# Power.net
KiCad netlist of a schematic drawn in Altium Designer
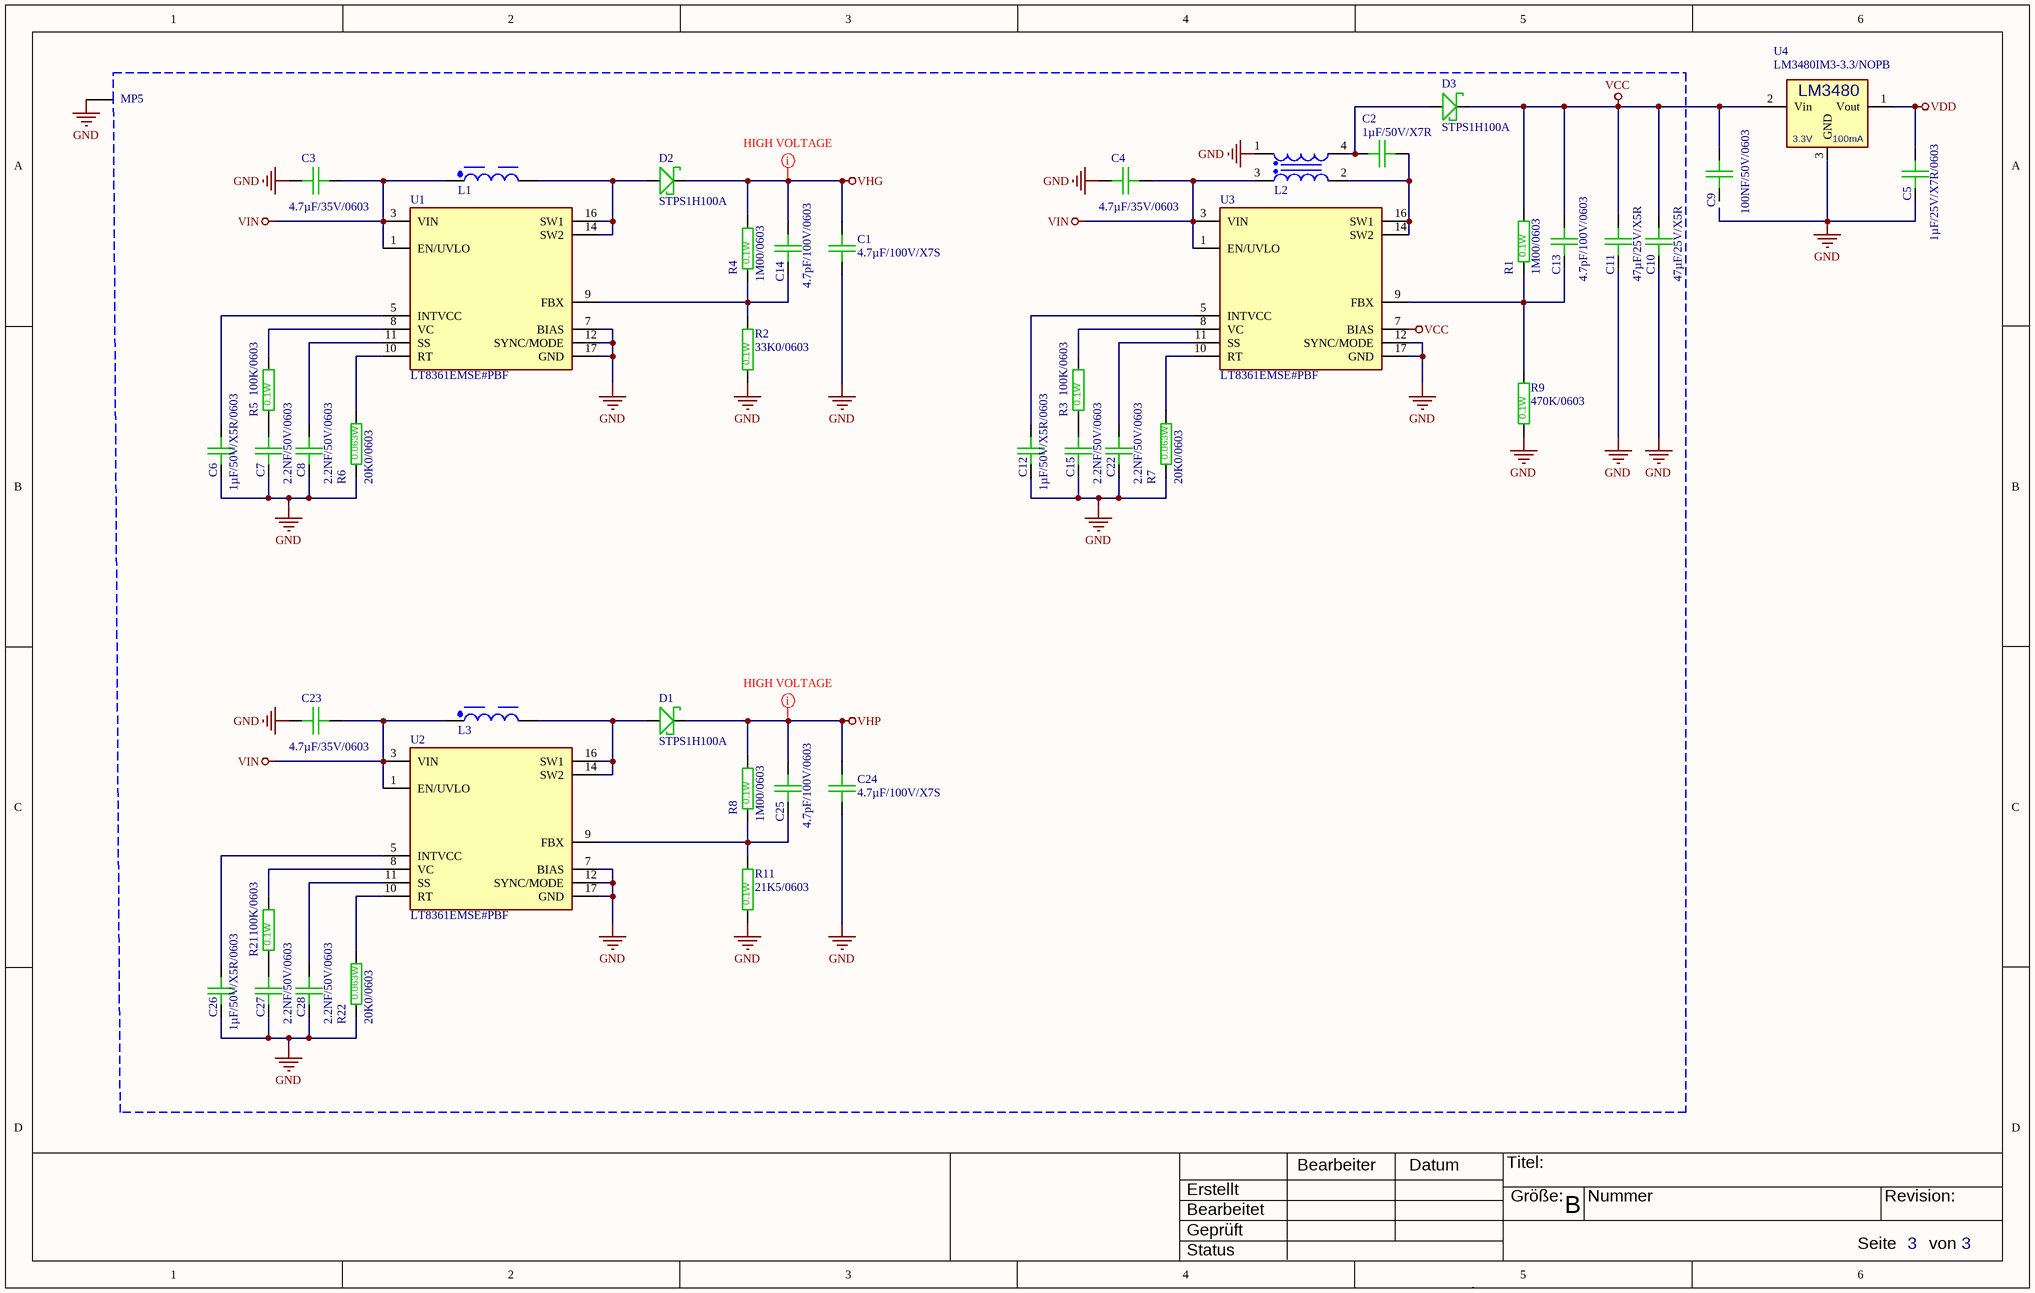
[diagram p0: Power.Schdoc]

(export (version "E")
  (design (tool "Eeschema 10.0.6"))
  (components
    (comp (ref "C1")
      (value "4.7µF/100V/X7S")
      (footprint "1206__R")
      (description "Capacitor, 4.7µF/100V, 10%, Ceramic X7S, SMD, 1206")
      (fields
        (field (name "MANUFACTURER") "Murata")
        (field (name "MANUFACTURER PART NUMBER") "GRM31CC72A475KE11L")
      )
      (libsource (lib "SCH_SMD_Passive_Capacitor_1206") (part "4.7µF/100V/X7S"))
    )
    (comp (ref "C2")
      (value "1µF/50V/X7R")
      (footprint "1206__R")
      (description "Capacitor, 1µF/50V, 10%, Ceramic X7R, SMD, 1206")
      (libsource (lib "SCH_SMD_Passive_Capacitor_1206") (part "1µF/50V"))
    )
    (comp (ref "C3")
      (value "4.7µF/35V/0603")
      (footprint "0603__R")
      (description "Capacitor, 4.7µF, 35V, 10%, Ceramic X5R, SMD, 0603, Low ESR")
      (fields
        (field (name "MANUFACTURER") "TDK")
        (field (name "MANUFACTURER PART NUMBER") "C1608X5R1V475K080AC")
      )
      (libsource (lib "SCH_SMD_Passive_Capacitor_0603") (part "4.7µF/35V/0603"))
    )
    (comp (ref "C4")
      (value "4.7µF/35V/0603")
      (footprint "0603__R")
      (description "Capacitor, 4.7µF, 35V, 10%, Ceramic X5R, SMD, 0603, Low ESR")
      (fields
        (field (name "MANUFACTURER") "TDK")
        (field (name "MANUFACTURER PART NUMBER") "C1608X5R1V475K080AC")
      )
      (libsource (lib "SCH_SMD_Passive_Capacitor_0603") (part "4.7µF/35V/0603"))
    )
    (comp (ref "C5")
      (value "1µF/25V/X7R/0603")
      (footprint "0603__R")
      (description "Capacitor, 1µF, 25V, X7R, 10%, Ceramic, SMD, 0603")
      (fields
        (field (name "MANUFACTURER") "Taiyo Yuden")
        (field (name "MANUFACTURER PART NUMBER") "TMK107B7105KA-T")
      )
      (libsource (lib "SCH_SMD_Passive_Capacitor_0603") (part "1µF/25V/X7R/0603"))
    )
    (comp (ref "C6")
      (value "1µF/50V/X5R/0603")
      (footprint "0603__R")
      (description "Capacitor, 1µF, 50V, X5R, 10%, Ceramic, SMD, 0603")
      (libsource (lib "SCH_SMD_Passive_Capacitor_0603") (part "1µF/50V/X5R/0603"))
    )
    (comp (ref "C7")
      (value "2.2NF/50V/0603")
      (footprint "0603__R")
      (description "Capacitor, 2.2nF, 50V, 10%, Ceramic, SMD, 0603")
      (fields
        (field (name "MANUFACTURER") "KEMET")
        (field (name "MANUFACTURER PART NUMBER") "C0603C222K5RAC   TU")
      )
      (libsource (lib "SCH_SMD_Passive_Capacitor_0603") (part "2.2NF/50V/0603"))
    )
    (comp (ref "C8")
      (value "2.2NF/50V/0603")
      (footprint "0603__R")
      (description "Capacitor, 2.2nF, 50V, 10%, Ceramic, SMD, 0603")
      (fields
        (field (name "MANUFACTURER") "KEMET")
        (field (name "MANUFACTURER PART NUMBER") "C0603C222K5RAC   TU")
      )
      (libsource (lib "SCH_SMD_Passive_Capacitor_0603") (part "2.2NF/50V/0603"))
    )
    (comp (ref "C9")
      (value "100NF/50V/0603")
      (footprint "0603__R")
      (description "Capacitor, 100nF, 50V, 10%, Ceramic XR7, SMD, 0603")
      (fields
        (field (name "MANUFACTURER") "KEMET")
        (field (name "MANUFACTURER PART NUMBER") "C0603X104K5RACTU")
      )
      (libsource (lib "SCH_SMD_Passive_Capacitor_0603") (part "100NF/50V/0603"))
    )
    (comp (ref "C10")
      (value "47µF/25V/X5R")
      (footprint "1206__R")
      (description "Capacitor, 47µF/25V, 20%, Ceramic X5R, SMD, 1206")
      (fields
        (field (name "MANUFACTURER") "TDK")
        (field (name "MANUFACTURER PART NUMBER") "C3216X5R1E476M160AC")
      )
      (libsource (lib "SCH_SMD_Passive_Capacitor_1206") (part "47µF/25V/X5R"))
    )
    (comp (ref "C11")
      (value "47µF/25V/X5R")
      (footprint "1206__R")
      (description "Capacitor, 47µF/25V, 20%, Ceramic X5R, SMD, 1206")
      (fields
        (field (name "MANUFACTURER") "TDK")
        (field (name "MANUFACTURER PART NUMBER") "C3216X5R1E476M160AC")
      )
      (libsource (lib "SCH_SMD_Passive_Capacitor_1206") (part "47µF/25V/X5R"))
    )
    (comp (ref "C12")
      (value "1µF/50V/X5R/0603")
      (footprint "0603__R")
      (description "Capacitor, 1µF, 50V, X5R, 10%, Ceramic, SMD, 0603")
      (libsource (lib "SCH_SMD_Passive_Capacitor_0603") (part "1µF/50V/X5R/0603"))
    )
    (comp (ref "C13")
      (value "4.7pF/100V/0603")
      (footprint "0603__R")
      (description "Capacitor, 4.7pF, 100V, 10%, Ceramic, SMD, 0603")
      (libsource (lib "SCH_SMD_Passive_Capacitor_0603") (part "4.7NF/50V/0603"))
    )
    (comp (ref "C14")
      (value "4.7pF/100V/0603")
      (footprint "0603__R")
      (description "Capacitor, 4.7pF, 100V, 10%, Ceramic, SMD, 0603")
      (libsource (lib "SCH_SMD_Passive_Capacitor_0603") (part "4.7NF/50V/0603"))
    )
    (comp (ref "C15")
      (value "2.2NF/50V/0603")
      (footprint "0603__R")
      (description "Capacitor, 2.2nF, 50V, 10%, Ceramic, SMD, 0603")
      (fields
        (field (name "MANUFACTURER") "KEMET")
        (field (name "MANUFACTURER PART NUMBER") "C0603C222K5RAC   TU")
      )
      (libsource (lib "SCH_SMD_Passive_Capacitor_0603") (part "2.2NF/50V/0603"))
    )
    (comp (ref "C22")
      (value "2.2NF/50V/0603")
      (footprint "0603__R")
      (description "Capacitor, 2.2nF, 50V, 10%, Ceramic, SMD, 0603")
      (fields
        (field (name "MANUFACTURER") "KEMET")
        (field (name "MANUFACTURER PART NUMBER") "C0603C222K5RAC   TU")
      )
      (libsource (lib "SCH_SMD_Passive_Capacitor_0603") (part "2.2NF/50V/0603"))
    )
    (comp (ref "C23")
      (value "4.7µF/35V/0603")
      (footprint "0603__R")
      (description "Capacitor, 4.7µF, 35V, 10%, Ceramic X5R, SMD, 0603, Low ESR")
      (fields
        (field (name "MANUFACTURER") "TDK")
        (field (name "MANUFACTURER PART NUMBER") "C1608X5R1V475K080AC")
      )
      (libsource (lib "SCH_SMD_Passive_Capacitor_0603") (part "4.7µF/35V/0603"))
    )
    (comp (ref "C24")
      (value "4.7µF/100V/X7S")
      (footprint "1206__R")
      (description "Capacitor, 4.7µF/100V, 10%, Ceramic X7S, SMD, 1206")
      (fields
        (field (name "MANUFACTURER") "Murata")
        (field (name "MANUFACTURER PART NUMBER") "GRM31CC72A475KE11L")
      )
      (libsource (lib "SCH_SMD_Passive_Capacitor_1206") (part "4.7µF/100V/X7S"))
    )
    (comp (ref "C25")
      (value "4.7pF/100V/0603")
      (footprint "0603__R")
      (description "Capacitor, 4.7pF, 100V, 10%, Ceramic, SMD, 0603")
      (libsource (lib "SCH_SMD_Passive_Capacitor_0603") (part "4.7NF/50V/0603"))
    )
    (comp (ref "C26")
      (value "1µF/50V/X5R/0603")
      (footprint "0603__R")
      (description "Capacitor, 1µF, 50V, X5R, 10%, Ceramic, SMD, 0603")
      (libsource (lib "SCH_SMD_Passive_Capacitor_0603") (part "1µF/50V/X5R/0603"))
    )
    (comp (ref "C27")
      (value "2.2NF/50V/0603")
      (footprint "0603__R")
      (description "Capacitor, 2.2nF, 50V, 10%, Ceramic, SMD, 0603")
      (fields
        (field (name "MANUFACTURER") "KEMET")
        (field (name "MANUFACTURER PART NUMBER") "C0603C222K5RAC   TU")
      )
      (libsource (lib "SCH_SMD_Passive_Capacitor_0603") (part "2.2NF/50V/0603"))
    )
    (comp (ref "C28")
      (value "2.2NF/50V/0603")
      (footprint "0603__R")
      (description "Capacitor, 2.2nF, 50V, 10%, Ceramic, SMD, 0603")
      (fields
        (field (name "MANUFACTURER") "KEMET")
        (field (name "MANUFACTURER PART NUMBER") "C0603C222K5RAC   TU")
      )
      (libsource (lib "SCH_SMD_Passive_Capacitor_0603") (part "2.2NF/50V/0603"))
    )
    (comp (ref "D1")
      (value "STPS1H100A")
      (footprint "SMA__R")
      (description "DIODE SCHOTTKY 100V 1A SMA")
      (fields
        (field (name "MANUFACTURER") "STMicroelectronics")
        (field (name "MANUFACTURER PART NUMBER") "STPS1H100A")
      )
      (libsource (lib "SCH_SMD_Active_Diode") (part "STPS1H100A"))
    )
    (comp (ref "D2")
      (value "STPS1H100A")
      (footprint "SMA__R")
      (description "DIODE SCHOTTKY 100V 1A SMA")
      (fields
        (field (name "MANUFACTURER") "STMicroelectronics")
        (field (name "MANUFACTURER PART NUMBER") "STPS1H100A")
      )
      (libsource (lib "SCH_SMD_Active_Diode") (part "STPS1H100A"))
    )
    (comp (ref "D3")
      (value "STPS1H100A")
      (footprint "SMA__R")
      (description "DIODE SCHOTTKY 100V 1A SMA")
      (fields
        (field (name "MANUFACTURER") "STMicroelectronics")
        (field (name "MANUFACTURER PART NUMBER") "STPS1H100A")
      )
      (libsource (lib "SCH_SMD_Active_Diode") (part "STPS1H100A"))
    )
    (comp (ref "L1")
      (value "6.8µH, 2.4A")
      (footprint "WE-TPC_8020")
      (description "WE-TPC SMT Tiny Power Inductor, size 8020, 6.8µH, 2.4A, 68mΩ")
      (fields
        (field (name "MANUFACTURER PART NUMBER") "7440700068")
        (field (name "MANUFACTURER") "Wurth Elektronik")
      )
      (libsource (lib "GP1247AI") (part "7440700068"))
    )
    (comp (ref "L2")
      (value "6.8µH, 1.45A")
      (footprint "WE-TDC_8038")
      (description "WE-TDC SMT Shielded Coupled Inductor, size 8038, 6.8µH, 1.45A, 100mΩ")
      (fields
        (field (name "MANUFACTURER PART NUMBER") "74489440068")
        (field (name "MANUFACTURER") "Wurth Elektronik")
      )
      (libsource (lib "GP1247AI") (part "74489440068"))
    )
    (comp (ref "L3")
      (value "6.8µH, 2.4A")
      (footprint "WE-TPC_8020")
      (description "WE-TPC SMT Tiny Power Inductor, size 8020, 6.8µH, 2.4A, 68mΩ")
      (fields
        (field (name "MANUFACTURER PART NUMBER") "7440700068")
        (field (name "MANUFACTURER") "Wurth Elektronik")
      )
      (libsource (lib "GP1247AI") (part "7440700068"))
    )
    (comp (ref "MP5")
      (value "3670570")
      (footprint "3670570")
      (description "WE-SHC Shielding Cabinet, SMT Frame Seamless, Tin Plated, Tray, 57x31x6mm")
      (fields (field (name "MANUFACTURER") "Wurth Elektronik"))
      (libsource (lib "GP1247AI") (part "3670570"))
    )
    (comp (ref "R1")
      (value "1M00/0603")
      (footprint "0603__R")
      (description "Resistor, 1M00, 0,1 W, 1,0 %, TK50, Metallschicht, SMD, 0603")
      (libsource (lib "SCH_SMD_Passive_Resistor_0603") (part "1M00/0603"))
    )
    (comp (ref "R2")
      (value "33K0/0603")
      (footprint "0603__R")
      (description "Resistor, 33K, 0,1 W, 1,0 %, TK50, Metallschicht, SMD, 0603")
      (libsource (lib "SCH_SMD_Passive_Resistor_0603") (part "33K0/0603"))
    )
    (comp (ref "R3")
      (value "100K/0603")
      (footprint "0603__R")
      (description "Resistor, 100K, 0.1W, 1%, TK50, Metallschicht, SMD, 0603")
      (libsource (lib "SCH_SMD_Passive_Resistor_0603") (part "100K/0603"))
    )
    (comp (ref "R4")
      (value "1M00/0603")
      (footprint "0603__R")
      (description "Resistor, 1M00, 0,1 W, 1,0 %, TK50, Metallschicht, SMD, 0603")
      (libsource (lib "SCH_SMD_Passive_Resistor_0603") (part "1M00/0603"))
    )
    (comp (ref "R5")
      (value "100K/0603")
      (footprint "0603__R")
      (description "Resistor, 100K, 0.1W, 1%, TK50, Metallschicht, SMD, 0603")
      (libsource (lib "SCH_SMD_Passive_Resistor_0603") (part "100K/0603"))
    )
    (comp (ref "R6")
      (value "20K0/0603")
      (footprint "0603__R")
      (description "Resistor, 20K0, 0.063W, 1%, TK100, Metallschicht, SMD, 0603")
      (libsource (lib "SCH_SMD_Passive_Resistor_0603") (part "20K0/0603"))
    )
    (comp (ref "R7")
      (value "20K0/0603")
      (footprint "0603__R")
      (description "Resistor, 20K0, 0.063W, 1%, TK100, Metallschicht, SMD, 0603")
      (libsource (lib "SCH_SMD_Passive_Resistor_0603") (part "20K0/0603"))
    )
    (comp (ref "R8")
      (value "1M00/0603")
      (footprint "0603__R")
      (description "Resistor, 1M00, 0,1 W, 1,0 %, TK50, Metallschicht, SMD, 0603")
      (libsource (lib "SCH_SMD_Passive_Resistor_0603") (part "1M00/0603"))
    )
    (comp (ref "R9")
      (value "470K/0603")
      (footprint "0603__R")
      (description "Resistor, 470K, 0.1W, 1%, TK50, Metallschicht, SMD, 0603")
      (libsource (lib "SCH_SMD_Passive_Resistor_0603") (part "470K/0603"))
    )
    (comp (ref "R11")
      (value "21K5/0603")
      (footprint "0603__R")
      (description "Resistor, 21K5, 0.1W, 1%, TK50, Metallschicht, SMD, 0603")
      (libsource (lib "SCH_SMD_Passive_Resistor_0603") (part "22K0/0603"))
    )
    (comp (ref "R21")
      (value "100K/0603")
      (footprint "0603__R")
      (description "Resistor, 100K, 0.1W, 1%, TK50, Metallschicht, SMD, 0603")
      (libsource (lib "SCH_SMD_Passive_Resistor_0603") (part "100K/0603"))
    )
    (comp (ref "R22")
      (value "20K0/0603")
      (footprint "0603__R")
      (description "Resistor, 20K0, 0.063W, 1%, TK100, Metallschicht, SMD, 0603")
      (libsource (lib "SCH_SMD_Passive_Resistor_0603") (part "20K0/0603"))
    )
    (comp (ref "U1")
      (value "LT8361EMSE#PBF")
      (footprint "MSOP-16/12__R")
      (description "Conv DC-DC 2.8V to 60V Step Up Single-Out 100V 2A Automotive 12-Pin MSOP EP Tube")
      (fields (field (name "MOUSER PART NUMBER") "584-LT8361EMSE#PBF"))
      (libsource (lib "GP1247AI") (part "LT8361EMSE#PBF"))
    )
    (comp (ref "U2")
      (value "LT8361EMSE#PBF")
      (footprint "MSOP-16/12__R")
      (description "Conv DC-DC 2.8V to 60V Step Up Single-Out 100V 2A Automotive 12-Pin MSOP EP Tube")
      (fields (field (name "MOUSER PART NUMBER") "584-LT8361EMSE#PBF"))
      (libsource (lib "GP1247AI") (part "LT8361EMSE#PBF"))
    )
    (comp (ref "U3")
      (value "LT8361EMSE#PBF")
      (footprint "MSOP-16/12__R")
      (description "Conv DC-DC 2.8V to 60V Step Up Single-Out 100V 2A Automotive 12-Pin MSOP EP Tube")
      (fields (field (name "MOUSER PART NUMBER") "584-LT8361EMSE#PBF"))
      (libsource (lib "GP1247AI") (part "LT8361EMSE#PBF"))
    )
    (comp (ref "U4")
      (value "LM3480IM3-3.3/NOPB")
      (footprint "SOT-23-3_PW__R")
      (description "LDO, SOT-23, 3V3 OUT 100mA, Vinmax 30V, SMD")
      (fields (field (name "MANUFACTURER") "Texas Instruments"))
      (libsource (lib "altium-import") (part "root_0_LM3480IM3-3.3/NOPB_"))
    )
  )
  (nets
    (net (code "1") (name "GND") (class "Default")
      (node (ref "C1") (pin "1") (pinfunction "1_1") (pintype "passive"))
      (node (ref "C10") (pin "1") (pinfunction "1_1") (pintype "passive"))
      (node (ref "C11") (pin "1") (pinfunction "1_1") (pintype "passive"))
      (node (ref "C12") (pin "1") (pinfunction "1_1") (pintype "passive"))
      (node (ref "C15") (pin "1") (pinfunction "1_1") (pintype "passive"))
      (node (ref "C22") (pin "1") (pinfunction "1_1") (pintype "passive"))
      (node (ref "C23") (pin "2") (pinfunction "2_2") (pintype "passive"))
      (node (ref "C24") (pin "1") (pinfunction "1_1") (pintype "passive"))
      (node (ref "C26") (pin "1") (pinfunction "1_1") (pintype "passive"))
      (node (ref "C27") (pin "1") (pinfunction "1_1") (pintype "passive"))
      (node (ref "C28") (pin "1") (pinfunction "1_1") (pintype "passive"))
      (node (ref "C3") (pin "2") (pinfunction "2_2") (pintype "passive"))
      (node (ref "C4") (pin "2") (pinfunction "2_2") (pintype "passive"))
      (node (ref "C5") (pin "1") (pinfunction "1_1") (pintype "passive"))
      (node (ref "C6") (pin "1") (pinfunction "1_1") (pintype "passive"))
      (node (ref "C7") (pin "1") (pinfunction "1_1") (pintype "passive"))
      (node (ref "C8") (pin "1") (pinfunction "1_1") (pintype "passive"))
      (node (ref "L2") (pin "1") (pinfunction "1_1") (pintype "passive"))
      (node (ref "MP5") (pin "1") (pinfunction "1_1") (pintype "passive"))
      (node (ref "R11") (pin "1") (pinfunction "1_1") (pintype "passive"))
      (node (ref "R2") (pin "1") (pinfunction "1_1") (pintype "passive"))
      (node (ref "R22") (pin "1") (pinfunction "1_1") (pintype "passive"))
      (node (ref "R6") (pin "1") (pinfunction "1_1") (pintype "passive"))
      (node (ref "R7") (pin "1") (pinfunction "1_1") (pintype "passive"))
      (node (ref "R9") (pin "1") (pinfunction "1_1") (pintype "passive"))
      (node (ref "U1") (pin "12") (pinfunction "SYNC/MODE_12") (pintype "passive"))
      (node (ref "U1") (pin "17") (pinfunction "GND_17") (pintype "passive"))
      (node (ref "U1") (pin "7") (pinfunction "BIAS_7") (pintype "passive"))
      (node (ref "U2") (pin "12") (pinfunction "SYNC/MODE_12") (pintype "passive"))
      (node (ref "U2") (pin "17") (pinfunction "GND_17") (pintype "passive"))
      (node (ref "U2") (pin "7") (pinfunction "BIAS_7") (pintype "passive"))
      (node (ref "U3") (pin "12") (pinfunction "SYNC/MODE_12") (pintype "passive"))
      (node (ref "U3") (pin "17") (pinfunction "GND_17") (pintype "passive"))
      (node (ref "U4") (pin "3") (pinfunction "GND_3") (pintype "power_in"))
    )
    (net (code "2") (name "Net-(C2-Pad2)") (class "Default")
      (node (ref "C2") (pin "2") (pinfunction "2_2") (pintype "passive"))
      (node (ref "D3") (pin "1") (pintype "passive"))
      (node (ref "L2") (pin "4") (pinfunction "4_4") (pintype "passive"))
    )
    (net (code "3") (name "Net-(C7-Pad2)") (class "Default")
      (node (ref "C7") (pin "2") (pinfunction "2_2") (pintype "passive"))
      (node (ref "R5") (pin "1") (pinfunction "1_1") (pintype "passive"))
    )
    (net (code "4") (name "Net-(C15-Pad2)") (class "Default")
      (node (ref "C15") (pin "2") (pinfunction "2_2") (pintype "passive"))
      (node (ref "R3") (pin "1") (pinfunction "1_1") (pintype "passive"))
    )
    (net (code "5") (name "Net-(C27-Pad2)") (class "Default")
      (node (ref "C27") (pin "2") (pinfunction "2_2") (pintype "passive"))
      (node (ref "R21") (pin "1") (pinfunction "1_1") (pintype "passive"))
    )
    (net (code "6") (name "Net-(U1-FBX)") (class "Default")
      (node (ref "C14") (pin "1") (pinfunction "1_1") (pintype "passive"))
      (node (ref "R2") (pin "2") (pinfunction "2_2") (pintype "passive"))
      (node (ref "R4") (pin "1") (pinfunction "1_1") (pintype "passive"))
      (node (ref "U1") (pin "9") (pinfunction "FBX_9") (pintype "passive"))
    )
    (net (code "7") (name "Net-(U1-INTVCC)") (class "Default")
      (node (ref "C6") (pin "2") (pinfunction "2_2") (pintype "passive"))
      (node (ref "U1") (pin "5") (pinfunction "INTVCC_5") (pintype "passive"))
    )
    (net (code "8") (name "Net-(U1-RT)") (class "Default")
      (node (ref "R6") (pin "2") (pinfunction "2_2") (pintype "passive"))
      (node (ref "U1") (pin "10") (pinfunction "RT_10") (pintype "passive"))
    )
    (net (code "9") (name "Net-(U1-SS)") (class "Default")
      (node (ref "C8") (pin "2") (pinfunction "2_2") (pintype "passive"))
      (node (ref "U1") (pin "11") (pinfunction "SS_11") (pintype "passive"))
    )
    (net (code "10") (name "Net-(U1-SW1)") (class "Default")
      (node (ref "D2") (pin "1") (pintype "passive"))
      (node (ref "L1") (pin "2") (pinfunction "2_2") (pintype "passive"))
      (node (ref "U1") (pin "14") (pinfunction "SW2_14") (pintype "passive"))
      (node (ref "U1") (pin "16") (pinfunction "SW1_16") (pintype "passive"))
    )
    (net (code "11") (name "Net-(U1-VC)") (class "Default")
      (node (ref "R5") (pin "2") (pinfunction "2_2") (pintype "passive"))
      (node (ref "U1") (pin "8") (pinfunction "VC_8") (pintype "passive"))
    )
    (net (code "12") (name "Net-(U2-FBX)") (class "Default")
      (node (ref "C25") (pin "1") (pinfunction "1_1") (pintype "passive"))
      (node (ref "R11") (pin "2") (pinfunction "2_2") (pintype "passive"))
      (node (ref "R8") (pin "1") (pinfunction "1_1") (pintype "passive"))
      (node (ref "U2") (pin "9") (pinfunction "FBX_9") (pintype "passive"))
    )
    (net (code "13") (name "Net-(U2-INTVCC)") (class "Default")
      (node (ref "C26") (pin "2") (pinfunction "2_2") (pintype "passive"))
      (node (ref "U2") (pin "5") (pinfunction "INTVCC_5") (pintype "passive"))
    )
    (net (code "14") (name "Net-(U2-RT)") (class "Default")
      (node (ref "R22") (pin "2") (pinfunction "2_2") (pintype "passive"))
      (node (ref "U2") (pin "10") (pinfunction "RT_10") (pintype "passive"))
    )
    (net (code "15") (name "Net-(U2-SS)") (class "Default")
      (node (ref "C28") (pin "2") (pinfunction "2_2") (pintype "passive"))
      (node (ref "U2") (pin "11") (pinfunction "SS_11") (pintype "passive"))
    )
    (net (code "16") (name "Net-(U2-SW1)") (class "Default")
      (node (ref "D1") (pin "1") (pintype "passive"))
      (node (ref "L3") (pin "2") (pinfunction "2_2") (pintype "passive"))
      (node (ref "U2") (pin "14") (pinfunction "SW2_14") (pintype "passive"))
      (node (ref "U2") (pin "16") (pinfunction "SW1_16") (pintype "passive"))
    )
    (net (code "17") (name "Net-(U2-VC)") (class "Default")
      (node (ref "R21") (pin "2") (pinfunction "2_2") (pintype "passive"))
      (node (ref "U2") (pin "8") (pinfunction "VC_8") (pintype "passive"))
    )
    (net (code "18") (name "Net-(U3-FBX)") (class "Default")
      (node (ref "C13") (pin "1") (pinfunction "1_1") (pintype "passive"))
      (node (ref "R1") (pin "1") (pinfunction "1_1") (pintype "passive"))
      (node (ref "R9") (pin "2") (pinfunction "2_2") (pintype "passive"))
      (node (ref "U3") (pin "9") (pinfunction "FBX_9") (pintype "passive"))
    )
    (net (code "19") (name "Net-(U3-INTVCC)") (class "Default")
      (node (ref "C12") (pin "2") (pinfunction "2_2") (pintype "passive"))
      (node (ref "U3") (pin "5") (pinfunction "INTVCC_5") (pintype "passive"))
    )
    (net (code "20") (name "Net-(U3-RT)") (class "Default")
      (node (ref "R7") (pin "2") (pinfunction "2_2") (pintype "passive"))
      (node (ref "U3") (pin "10") (pinfunction "RT_10") (pintype "passive"))
    )
    (net (code "21") (name "Net-(U3-SS)") (class "Default")
      (node (ref "C22") (pin "2") (pinfunction "2_2") (pintype "passive"))
      (node (ref "U3") (pin "11") (pinfunction "SS_11") (pintype "passive"))
    )
    (net (code "22") (name "Net-(U3-SW1)") (class "Default")
      (node (ref "C2") (pin "1") (pinfunction "1_1") (pintype "passive"))
      (node (ref "L2") (pin "2") (pinfunction "2_2") (pintype "passive"))
      (node (ref "U3") (pin "14") (pinfunction "SW2_14") (pintype "passive"))
      (node (ref "U3") (pin "16") (pinfunction "SW1_16") (pintype "passive"))
    )
    (net (code "23") (name "Net-(U3-VC)") (class "Default")
      (node (ref "R3") (pin "2") (pinfunction "2_2") (pintype "passive"))
      (node (ref "U3") (pin "8") (pinfunction "VC_8") (pintype "passive"))
    )
    (net (code "24") (name "VCC") (class "Default")
      (node (ref "C10") (pin "2") (pinfunction "2_2") (pintype "passive"))
      (node (ref "C11") (pin "2") (pinfunction "2_2") (pintype "passive"))
      (node (ref "C13") (pin "2") (pinfunction "2_2") (pintype "passive"))
      (node (ref "C9") (pin "2") (pinfunction "2_2") (pintype "passive"))
      (node (ref "D3") (pin "2") (pintype "passive"))
      (node (ref "R1") (pin "2") (pinfunction "2_2") (pintype "passive"))
      (node (ref "U3") (pin "7") (pinfunction "BIAS_7") (pintype "passive"))
      (node (ref "U4") (pin "2") (pinfunction "Vin_2") (pintype "passive"))
    )
    (net (code "25") (name "VDD") (class "Default")
      (node (ref "C5") (pin "2") (pinfunction "2_2") (pintype "passive"))
      (node (ref "U4") (pin "1") (pinfunction "Vout_1") (pintype "power_in"))
    )
    (net (code "26") (name "VHG") (class "Default")
      (node (ref "C1") (pin "2") (pinfunction "2_2") (pintype "passive"))
      (node (ref "C14") (pin "2") (pinfunction "2_2") (pintype "passive"))
      (node (ref "D2") (pin "2") (pintype "passive"))
      (node (ref "R4") (pin "2") (pinfunction "2_2") (pintype "passive"))
    )
    (net (code "27") (name "VHP") (class "Default")
      (node (ref "C24") (pin "2") (pinfunction "2_2") (pintype "passive"))
      (node (ref "C25") (pin "2") (pinfunction "2_2") (pintype "passive"))
      (node (ref "D1") (pin "2") (pintype "passive"))
      (node (ref "R8") (pin "2") (pinfunction "2_2") (pintype "passive"))
    )
    (net (code "28") (name "VIN") (class "Default")
      (node (ref "C23") (pin "1") (pinfunction "1_1") (pintype "passive"))
      (node (ref "C3") (pin "1") (pinfunction "1_1") (pintype "passive"))
      (node (ref "C4") (pin "1") (pinfunction "1_1") (pintype "passive"))
      (node (ref "L1") (pin "1") (pinfunction "1_1") (pintype "passive"))
      (node (ref "L2") (pin "3") (pinfunction "3_3") (pintype "passive"))
      (node (ref "L3") (pin "1") (pinfunction "1_1") (pintype "passive"))
      (node (ref "U1") (pin "1") (pinfunction "EN/UVLO_1") (pintype "passive"))
      (node (ref "U1") (pin "3") (pinfunction "VIN_3") (pintype "passive"))
      (node (ref "U2") (pin "1") (pinfunction "EN/UVLO_1") (pintype "passive"))
      (node (ref "U2") (pin "3") (pinfunction "VIN_3") (pintype "passive"))
      (node (ref "U3") (pin "1") (pinfunction "EN/UVLO_1") (pintype "passive"))
      (node (ref "U3") (pin "3") (pinfunction "VIN_3") (pintype "passive"))
    )
    (net (code "29") (name "unconnected-(C9-Pad1)") (class "Default")
      (node (ref "C9") (pin "1") (pinfunction "1_1") (pintype "passive"))
    )
    (net (code "30") (name "unconnected-(U1-NC-Pad6)") (class "Default")
      (node (ref "U1") (pin "6") (pinfunction "NC_6") (pintype "passive"))
    )
    (net (code "31") (name "unconnected-(U2-NC-Pad6)") (class "Default")
      (node (ref "U2") (pin "6") (pinfunction "NC_6") (pintype "passive"))
    )
    (net (code "32") (name "unconnected-(U3-NC-Pad6)") (class "Default")
      (node (ref "U3") (pin "6") (pinfunction "NC_6") (pintype "passive"))
    )
  )
)
